# bord.net
KiCad netlist of a schematic drawn in EAGLE
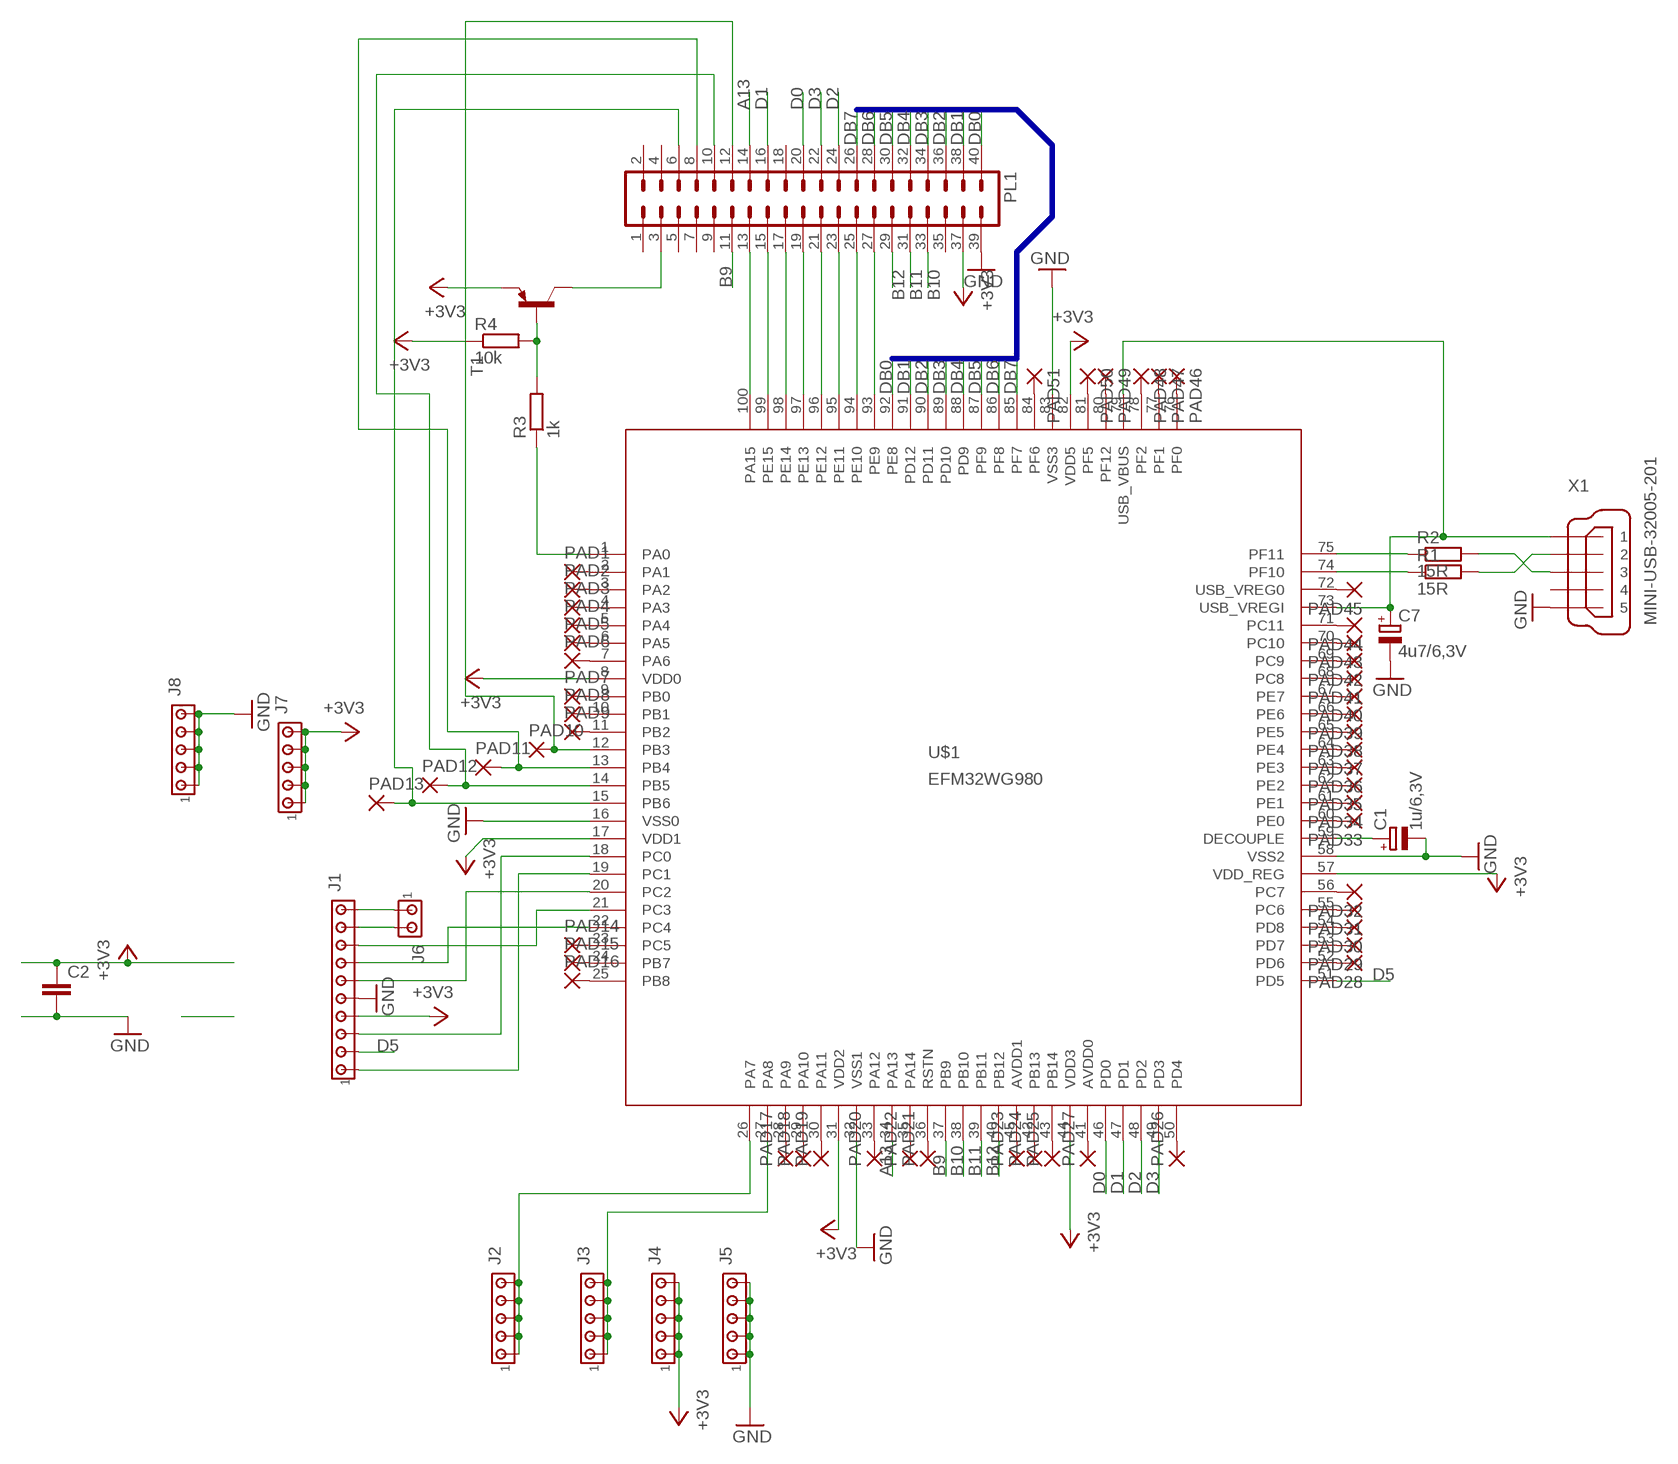
[diagram p0: schematic, sheet 1]

(export (version "E")
  (design (tool "Eeschema 10.0.6"))
  (components
    (comp (ref "C1")
      (value "1u/6,3V")
      (footprint "eagle-import:SMC_B")
      (libsource (lib "eagle-import") (part "CPOL-EUSMCB"))
    )
    (comp (ref "C2")
      (value "C-EUC0603")
      (footprint "eagle-import:C0603")
      (libsource (lib "eagle-import") (part "C-EUC0603"))
    )
    (comp (ref "C7")
      (value "4u7/6,3V")
      (footprint "eagle-import:SMC_B")
      (libsource (lib "eagle-import") (part "CPOL-EUSMCB"))
    )
    (comp (ref "J1")
      (value "MTA10-100")
      (footprint "eagle-import:10X10MTA")
      (libsource (lib "eagle-import") (part "MTA10-100"))
    )
    (comp (ref "J2")
      (value "MTA05-100")
      (footprint "eagle-import:10X05MTA")
      (libsource (lib "eagle-import") (part "MTA05-100"))
    )
    (comp (ref "J3")
      (value "MTA05-100")
      (footprint "eagle-import:10X05MTA")
      (libsource (lib "eagle-import") (part "MTA05-100"))
    )
    (comp (ref "J4")
      (value "MTA05-100")
      (footprint "eagle-import:10X05MTA")
      (libsource (lib "eagle-import") (part "MTA05-100"))
    )
    (comp (ref "J5")
      (value "MTA05-100")
      (footprint "eagle-import:10X05MTA")
      (libsource (lib "eagle-import") (part "MTA05-100"))
    )
    (comp (ref "J6")
      (value "MTA02-100")
      (footprint "eagle-import:10X02MTA")
      (libsource (lib "eagle-import") (part "MTA02-100"))
    )
    (comp (ref "J7")
      (value "MTA05-100")
      (footprint "eagle-import:10X05MTA")
      (libsource (lib "eagle-import") (part "MTA05-100"))
    )
    (comp (ref "J8")
      (value "MTA05-100")
      (footprint "eagle-import:10X05MTA")
      (libsource (lib "eagle-import") (part "MTA05-100"))
    )
    (comp (ref "PAD1")
      (value "1,6/0,8")
      (footprint "eagle-import:1,6_0,8")
      (libsource (lib "eagle-import") (part "1,6/0,8"))
    )
    (comp (ref "PAD2")
      (value "1,6/0,8")
      (footprint "eagle-import:1,6_0,8")
      (libsource (lib "eagle-import") (part "1,6/0,8"))
    )
    (comp (ref "PAD3")
      (value "1,6/0,8")
      (footprint "eagle-import:1,6_0,8")
      (libsource (lib "eagle-import") (part "1,6/0,8"))
    )
    (comp (ref "PAD4")
      (value "1,6/0,8")
      (footprint "eagle-import:1,6_0,8")
      (libsource (lib "eagle-import") (part "1,6/0,8"))
    )
    (comp (ref "PAD5")
      (value "1,6/0,8")
      (footprint "eagle-import:1,6_0,8")
      (libsource (lib "eagle-import") (part "1,6/0,8"))
    )
    (comp (ref "PAD6")
      (value "1,6/0,8")
      (footprint "eagle-import:1,6_0,8")
      (libsource (lib "eagle-import") (part "1,6/0,8"))
    )
    (comp (ref "PAD7")
      (value "1,6/0,8")
      (footprint "eagle-import:1,6_0,8")
      (libsource (lib "eagle-import") (part "1,6/0,8"))
    )
    (comp (ref "PAD8")
      (value "1,6/0,8")
      (footprint "eagle-import:1,6_0,8")
      (libsource (lib "eagle-import") (part "1,6/0,8"))
    )
    (comp (ref "PAD9")
      (value "1,6/0,8")
      (footprint "eagle-import:1,6_0,8")
      (libsource (lib "eagle-import") (part "1,6/0,8"))
    )
    (comp (ref "PAD10")
      (value "1,6/0,8")
      (footprint "eagle-import:1,6_0,8")
      (libsource (lib "eagle-import") (part "1,6/0,8"))
    )
    (comp (ref "PAD11")
      (value "1,6/0,8")
      (footprint "eagle-import:1,6_0,8")
      (libsource (lib "eagle-import") (part "1,6/0,8"))
    )
    (comp (ref "PAD12")
      (value "1,6/0,8")
      (footprint "eagle-import:1,6_0,8")
      (libsource (lib "eagle-import") (part "1,6/0,8"))
    )
    (comp (ref "PAD13")
      (value "1,6/0,8")
      (footprint "eagle-import:1,6_0,8")
      (libsource (lib "eagle-import") (part "1,6/0,8"))
    )
    (comp (ref "PAD14")
      (value "1,6/0,8")
      (footprint "eagle-import:1,6_0,8")
      (libsource (lib "eagle-import") (part "1,6/0,8"))
    )
    (comp (ref "PAD15")
      (value "1,6/0,8")
      (footprint "eagle-import:1,6_0,8")
      (libsource (lib "eagle-import") (part "1,6/0,8"))
    )
    (comp (ref "PAD16")
      (value "1,6/0,8")
      (footprint "eagle-import:1,6_0,8")
      (libsource (lib "eagle-import") (part "1,6/0,8"))
    )
    (comp (ref "PAD17")
      (value "1,6/0,8")
      (footprint "eagle-import:1,6_0,8")
      (libsource (lib "eagle-import") (part "1,6/0,8"))
    )
    (comp (ref "PAD18")
      (value "1,6/0,8")
      (footprint "eagle-import:1,6_0,8")
      (libsource (lib "eagle-import") (part "1,6/0,8"))
    )
    (comp (ref "PAD19")
      (value "1,6/0,8")
      (footprint "eagle-import:1,6_0,8")
      (libsource (lib "eagle-import") (part "1,6/0,8"))
    )
    (comp (ref "PAD20")
      (value "1,6/0,8")
      (footprint "eagle-import:1,6_0,8")
      (libsource (lib "eagle-import") (part "1,6/0,8"))
    )
    (comp (ref "PAD21")
      (value "1,6/0,8")
      (footprint "eagle-import:1,6_0,8")
      (libsource (lib "eagle-import") (part "1,6/0,8"))
    )
    (comp (ref "PAD22")
      (value "1,6/0,8")
      (footprint "eagle-import:1,6_0,8")
      (libsource (lib "eagle-import") (part "1,6/0,8"))
    )
    (comp (ref "PAD23")
      (value "1,6/0,8")
      (footprint "eagle-import:1,6_0,8")
      (libsource (lib "eagle-import") (part "1,6/0,8"))
    )
    (comp (ref "PAD24")
      (value "1,6/0,8")
      (footprint "eagle-import:1,6_0,8")
      (libsource (lib "eagle-import") (part "1,6/0,8"))
    )
    (comp (ref "PAD25")
      (value "1,6/0,8")
      (footprint "eagle-import:1,6_0,8")
      (libsource (lib "eagle-import") (part "1,6/0,8"))
    )
    (comp (ref "PAD26")
      (value "1,6/0,8")
      (footprint "eagle-import:1,6_0,8")
      (libsource (lib "eagle-import") (part "1,6/0,8"))
    )
    (comp (ref "PAD27")
      (value "1,6/0,8")
      (footprint "eagle-import:1,6_0,8")
      (libsource (lib "eagle-import") (part "1,6/0,8"))
    )
    (comp (ref "PAD28")
      (value "1,6/0,8")
      (footprint "eagle-import:1,6_0,8")
      (libsource (lib "eagle-import") (part "1,6/0,8"))
    )
    (comp (ref "PAD29")
      (value "1,6/0,8")
      (footprint "eagle-import:1,6_0,8")
      (libsource (lib "eagle-import") (part "1,6/0,8"))
    )
    (comp (ref "PAD30")
      (value "1,6/0,8")
      (footprint "eagle-import:1,6_0,8")
      (libsource (lib "eagle-import") (part "1,6/0,8"))
    )
    (comp (ref "PAD31")
      (value "1,6/0,8")
      (footprint "eagle-import:1,6_0,8")
      (libsource (lib "eagle-import") (part "1,6/0,8"))
    )
    (comp (ref "PAD32")
      (value "1,6/0,8")
      (footprint "eagle-import:1,6_0,8")
      (libsource (lib "eagle-import") (part "1,6/0,8"))
    )
    (comp (ref "PAD33")
      (value "1,6/0,8")
      (footprint "eagle-import:1,6_0,8")
      (libsource (lib "eagle-import") (part "1,6/0,8"))
    )
    (comp (ref "PAD34")
      (value "1,6/0,8")
      (footprint "eagle-import:1,6_0,8")
      (libsource (lib "eagle-import") (part "1,6/0,8"))
    )
    (comp (ref "PAD35")
      (value "1,6/0,8")
      (footprint "eagle-import:1,6_0,8")
      (libsource (lib "eagle-import") (part "1,6/0,8"))
    )
    (comp (ref "PAD36")
      (value "1,6/0,8")
      (footprint "eagle-import:1,6_0,8")
      (libsource (lib "eagle-import") (part "1,6/0,8"))
    )
    (comp (ref "PAD37")
      (value "1,6/0,8")
      (footprint "eagle-import:1,6_0,8")
      (libsource (lib "eagle-import") (part "1,6/0,8"))
    )
    (comp (ref "PAD38")
      (value "1,6/0,8")
      (footprint "eagle-import:1,6_0,8")
      (libsource (lib "eagle-import") (part "1,6/0,8"))
    )
    (comp (ref "PAD39")
      (value "1,6/0,8")
      (footprint "eagle-import:1,6_0,8")
      (libsource (lib "eagle-import") (part "1,6/0,8"))
    )
    (comp (ref "PAD40")
      (value "1,6/0,8")
      (footprint "eagle-import:1,6_0,8")
      (libsource (lib "eagle-import") (part "1,6/0,8"))
    )
    (comp (ref "PAD41")
      (value "1,6/0,8")
      (footprint "eagle-import:1,6_0,8")
      (libsource (lib "eagle-import") (part "1,6/0,8"))
    )
    (comp (ref "PAD42")
      (value "1,6/0,8")
      (footprint "eagle-import:1,6_0,8")
      (libsource (lib "eagle-import") (part "1,6/0,8"))
    )
    (comp (ref "PAD43")
      (value "1,6/0,8")
      (footprint "eagle-import:1,6_0,8")
      (libsource (lib "eagle-import") (part "1,6/0,8"))
    )
    (comp (ref "PAD44")
      (value "1,6/0,8")
      (footprint "eagle-import:1,6_0,8")
      (libsource (lib "eagle-import") (part "1,6/0,8"))
    )
    (comp (ref "PAD45")
      (value "1,6/0,8")
      (footprint "eagle-import:1,6_0,8")
      (libsource (lib "eagle-import") (part "1,6/0,8"))
    )
    (comp (ref "PAD46")
      (value "1,6/0,8")
      (footprint "eagle-import:1,6_0,8")
      (libsource (lib "eagle-import") (part "1,6/0,8"))
    )
    (comp (ref "PAD47")
      (value "1,6/0,8")
      (footprint "eagle-import:1,6_0,8")
      (libsource (lib "eagle-import") (part "1,6/0,8"))
    )
    (comp (ref "PAD48")
      (value "1,6/0,8")
      (footprint "eagle-import:1,6_0,8")
      (libsource (lib "eagle-import") (part "1,6/0,8"))
    )
    (comp (ref "PAD49")
      (value "1,6/0,8")
      (footprint "eagle-import:1,6_0,8")
      (libsource (lib "eagle-import") (part "1,6/0,8"))
    )
    (comp (ref "PAD50")
      (value "1,6/0,8")
      (footprint "eagle-import:1,6_0,8")
      (libsource (lib "eagle-import") (part "1,6/0,8"))
    )
    (comp (ref "PAD51")
      (value "1,6/0,8")
      (footprint "eagle-import:1,6_0,8")
      (libsource (lib "eagle-import") (part "1,6/0,8"))
    )
    (comp (ref "PL1")
      (value "40V")
      (footprint "eagle-import:40V")
      (libsource (lib "eagle-import") (part "40V"))
    )
    (comp (ref "R1")
      (value "15R")
      (footprint "eagle-import:M0805")
      (libsource (lib "eagle-import") (part "R-EU_M0805"))
    )
    (comp (ref "R2")
      (value "15R")
      (footprint "eagle-import:M0805")
      (libsource (lib "eagle-import") (part "R-EU_M0805"))
    )
    (comp (ref "R3")
      (value "1k")
      (footprint "eagle-import:M0805")
      (libsource (lib "eagle-import") (part "R-EU_M0805"))
    )
    (comp (ref "R4")
      (value "10k")
      (footprint "eagle-import:M0805")
      (libsource (lib "eagle-import") (part "R-EU_M0805"))
    )
    (comp (ref "T1")
      (value "BC807-16-PNP-SOT23-BEC")
      (footprint "eagle-import:SOT23-BEC")
      (libsource (lib "eagle-import") (part "-PNP-SOT23-BECBC807-16"))
    )
    (comp (ref "U$1")
      (value "EFM32WG980")
      (footprint "eagle-import:LQFP100")
      (libsource (lib "eagle-import") (part "EFM32WG980"))
    )
    (comp (ref "X1")
      (value "MINI-USB-32005-201")
      (footprint "eagle-import:32005-201")
      (libsource (lib "eagle-import") (part "MINI-USB-32005-201"))
    )
  )
  (nets
    (net (code "1") (name "+3V3") (class "Default")
      (node (ref "C2") (pin "1") (pinfunction "1_1") (pintype "passive"))
      (node (ref "J1") (pin "4") (pinfunction "4_4") (pintype "passive"))
      (node (ref "J4") (pin "1") (pinfunction "1_1") (pintype "passive"))
      (node (ref "J4") (pin "2") (pinfunction "2_2") (pintype "passive"))
      (node (ref "J4") (pin "3") (pinfunction "3_3") (pintype "passive"))
      (node (ref "J4") (pin "4") (pinfunction "4_4") (pintype "passive"))
      (node (ref "J4") (pin "5") (pinfunction "5_5") (pintype "passive"))
      (node (ref "J7") (pin "1") (pinfunction "1_1") (pintype "passive"))
      (node (ref "J7") (pin "2") (pinfunction "2_2") (pintype "passive"))
      (node (ref "J7") (pin "3") (pinfunction "3_3") (pintype "passive"))
      (node (ref "J7") (pin "4") (pinfunction "4_4") (pintype "passive"))
      (node (ref "J7") (pin "5") (pinfunction "5_5") (pintype "passive"))
      (node (ref "PL1") (pin "37") (pinfunction "37_37") (pintype "passive"))
      (node (ref "R4") (pin "1") (pinfunction "1_1") (pintype "passive"))
      (node (ref "T1") (pin "E") (pinfunction "E_E") (pintype "passive"))
      (node (ref "U$1") (pin "17") (pinfunction "VDD1_17") (pintype "power_in"))
      (node (ref "U$1") (pin "31") (pinfunction "VDD2_31") (pintype "power_in"))
      (node (ref "U$1") (pin "44") (pinfunction "VDD3_44") (pintype "power_in"))
      (node (ref "U$1") (pin "57") (pinfunction "VDD_REG_57") (pintype "power_in"))
      (node (ref "U$1") (pin "8") (pinfunction "VDD0_8") (pintype "power_in"))
      (node (ref "U$1") (pin "82") (pinfunction "VDD5_82") (pintype "power_in"))
    )
    (net (code "2") (name "/A13") (class "Default")
      (node (ref "PL1") (pin "14") (pinfunction "14_14") (pintype "passive"))
      (node (ref "U$1") (pin "34") (pinfunction "PA13_34") (pintype "bidirectional"))
    )
    (net (code "3") (name "/B9") (class "Default")
      (node (ref "PL1") (pin "11") (pinfunction "11_11") (pintype "passive"))
      (node (ref "U$1") (pin "37") (pinfunction "PB9_37") (pintype "bidirectional"))
    )
    (net (code "4") (name "/B10") (class "Default")
      (node (ref "PL1") (pin "33") (pinfunction "33_33") (pintype "passive"))
      (node (ref "U$1") (pin "38") (pinfunction "PB10_38") (pintype "bidirectional"))
    )
    (net (code "5") (name "/B11") (class "Default")
      (node (ref "PL1") (pin "31") (pinfunction "31_31") (pintype "passive"))
      (node (ref "U$1") (pin "39") (pinfunction "PB11_39") (pintype "bidirectional"))
    )
    (net (code "6") (name "/B12") (class "Default")
      (node (ref "PL1") (pin "29") (pinfunction "29_29") (pintype "passive"))
      (node (ref "U$1") (pin "40") (pinfunction "PB12_40") (pintype "bidirectional"))
    )
    (net (code "7") (name "/D0") (class "Default")
      (node (ref "PL1") (pin "20") (pinfunction "20_20") (pintype "passive"))
      (node (ref "U$1") (pin "46") (pinfunction "PD0_46") (pintype "bidirectional"))
    )
    (net (code "8") (name "/D1") (class "Default")
      (node (ref "PL1") (pin "16") (pinfunction "16_16") (pintype "passive"))
      (node (ref "U$1") (pin "47") (pinfunction "PD1_47") (pintype "bidirectional"))
    )
    (net (code "9") (name "/D2") (class "Default")
      (node (ref "PL1") (pin "24") (pinfunction "24_24") (pintype "passive"))
      (node (ref "U$1") (pin "48") (pinfunction "PD2_48") (pintype "bidirectional"))
    )
    (net (code "10") (name "/D3") (class "Default")
      (node (ref "PL1") (pin "22") (pinfunction "22_22") (pintype "passive"))
      (node (ref "U$1") (pin "49") (pinfunction "PD3_49") (pintype "bidirectional"))
    )
    (net (code "11") (name "/D5") (class "Default")
      (node (ref "J1") (pin "2") (pinfunction "2_2") (pintype "passive"))
      (node (ref "U$1") (pin "51") (pinfunction "PD5_51") (pintype "bidirectional"))
    )
    (net (code "12") (name "/DB0") (class "Default")
      (node (ref "PL1") (pin "40") (pinfunction "40_40") (pintype "passive"))
      (node (ref "U$1") (pin "92") (pinfunction "PE8_92") (pintype "bidirectional"))
    )
    (net (code "13") (name "/DB1") (class "Default")
      (node (ref "PL1") (pin "38") (pinfunction "38_38") (pintype "passive"))
      (node (ref "U$1") (pin "91") (pinfunction "PD12_91") (pintype "bidirectional"))
    )
    (net (code "14") (name "/DB2") (class "Default")
      (node (ref "PL1") (pin "36") (pinfunction "36_36") (pintype "passive"))
      (node (ref "U$1") (pin "90") (pinfunction "PD11_90") (pintype "power_in"))
    )
    (net (code "15") (name "/DB3") (class "Default")
      (node (ref "PL1") (pin "34") (pinfunction "34_34") (pintype "passive"))
      (node (ref "U$1") (pin "89") (pinfunction "PD10_89") (pintype "bidirectional"))
    )
    (net (code "16") (name "/DB4") (class "Default")
      (node (ref "PL1") (pin "32") (pinfunction "32_32") (pintype "passive"))
      (node (ref "U$1") (pin "88") (pinfunction "PD9_88") (pintype "bidirectional"))
    )
    (net (code "17") (name "/DB5") (class "Default")
      (node (ref "PL1") (pin "30") (pinfunction "30_30") (pintype "passive"))
      (node (ref "U$1") (pin "87") (pinfunction "PF9_87") (pintype "bidirectional"))
    )
    (net (code "18") (name "/DB6") (class "Default")
      (node (ref "PL1") (pin "28") (pinfunction "28_28") (pintype "passive"))
      (node (ref "U$1") (pin "86") (pinfunction "PF8_86") (pintype "bidirectional"))
    )
    (net (code "19") (name "/DB7") (class "Default")
      (node (ref "PL1") (pin "26") (pinfunction "26_26") (pintype "passive"))
      (node (ref "U$1") (pin "85") (pinfunction "PF7_85") (pintype "bidirectional"))
    )
    (net (code "20") (name "GND") (class "Default")
      (node (ref "C1") (pin "-") (pinfunction "-_-") (pintype "passive"))
      (node (ref "C2") (pin "2") (pinfunction "2_2") (pintype "passive"))
      (node (ref "C7") (pin "-") (pinfunction "-_-") (pintype "passive"))
      (node (ref "J1") (pin "5") (pinfunction "5_5") (pintype "passive"))
      (node (ref "J5") (pin "1") (pinfunction "1_1") (pintype "passive"))
      (node (ref "J5") (pin "2") (pinfunction "2_2") (pintype "passive"))
      (node (ref "J5") (pin "3") (pinfunction "3_3") (pintype "passive"))
      (node (ref "J5") (pin "4") (pinfunction "4_4") (pintype "passive"))
      (node (ref "J5") (pin "5") (pinfunction "5_5") (pintype "passive"))
      (node (ref "J8") (pin "1") (pinfunction "1_1") (pintype "passive"))
      (node (ref "J8") (pin "2") (pinfunction "2_2") (pintype "passive"))
      (node (ref "J8") (pin "3") (pinfunction "3_3") (pintype "passive"))
      (node (ref "J8") (pin "4") (pinfunction "4_4") (pintype "passive"))
      (node (ref "J8") (pin "5") (pinfunction "5_5") (pintype "passive"))
      (node (ref "PL1") (pin "39") (pinfunction "39_39") (pintype "passive"))
      (node (ref "U$1") (pin "16") (pinfunction "VSS0_16") (pintype "power_in"))
      (node (ref "U$1") (pin "32") (pinfunction "VSS1_32") (pintype "power_in"))
      (node (ref "U$1") (pin "58") (pinfunction "VSS2_58") (pintype "power_in"))
      (node (ref "U$1") (pin "83") (pinfunction "VSS3_83") (pintype "bidirectional"))
      (node (ref "X1") (pin "5") (pinfunction "5_5") (pintype "passive"))
    )
    (net (code "21") (name "Net-(J1-Pad9)") (class "Default")
      (node (ref "J1") (pin "9") (pinfunction "9_9") (pintype "passive"))
      (node (ref "J6") (pin "2") (pinfunction "2_2") (pintype "passive"))
    )
    (net (code "22") (name "Net-(J1-Pad10)") (class "Default")
      (node (ref "J1") (pin "10") (pinfunction "10_10") (pintype "passive"))
      (node (ref "J6") (pin "1") (pinfunction "1_1") (pintype "passive"))
    )
    (net (code "23") (name "Net-(PAD1-P)") (class "Default")
      (node (ref "PAD1") (pin "1") (pinfunction "P_1") (pintype "passive"))
      (node (ref "U$1") (pin "2") (pinfunction "PA1_2") (pintype "bidirectional"))
    )
    (net (code "24") (name "Net-(PAD2-P)") (class "Default")
      (node (ref "PAD2") (pin "1") (pinfunction "P_1") (pintype "passive"))
      (node (ref "U$1") (pin "3") (pinfunction "PA2_3") (pintype "bidirectional"))
    )
    (net (code "25") (name "Net-(PAD3-P)") (class "Default")
      (node (ref "PAD3") (pin "1") (pinfunction "P_1") (pintype "passive"))
      (node (ref "U$1") (pin "4") (pinfunction "PA3_4") (pintype "bidirectional"))
    )
    (net (code "26") (name "Net-(PAD4-P)") (class "Default")
      (node (ref "PAD4") (pin "1") (pinfunction "P_1") (pintype "passive"))
      (node (ref "U$1") (pin "5") (pinfunction "PA4_5") (pintype "bidirectional"))
    )
    (net (code "27") (name "Net-(PAD5-P)") (class "Default")
      (node (ref "PAD5") (pin "1") (pinfunction "P_1") (pintype "passive"))
      (node (ref "U$1") (pin "6") (pinfunction "PA5_6") (pintype "bidirectional"))
    )
    (net (code "28") (name "Net-(PAD6-P)") (class "Default")
      (node (ref "PAD6") (pin "1") (pinfunction "P_1") (pintype "passive"))
      (node (ref "U$1") (pin "7") (pinfunction "PA6_7") (pintype "bidirectional"))
    )
    (net (code "29") (name "Net-(PAD7-P)") (class "Default")
      (node (ref "PAD7") (pin "1") (pinfunction "P_1") (pintype "passive"))
      (node (ref "U$1") (pin "9") (pinfunction "PB0_9") (pintype "bidirectional"))
    )
    (net (code "30") (name "Net-(PAD8-P)") (class "Default")
      (node (ref "PAD8") (pin "1") (pinfunction "P_1") (pintype "passive"))
      (node (ref "U$1") (pin "10") (pinfunction "PB1_10") (pintype "bidirectional"))
    )
    (net (code "31") (name "Net-(PAD9-P)") (class "Default")
      (node (ref "PAD9") (pin "1") (pinfunction "P_1") (pintype "passive"))
      (node (ref "U$1") (pin "11") (pinfunction "PB2_11") (pintype "bidirectional"))
    )
    (net (code "32") (name "Net-(PAD10-P)") (class "Default")
      (node (ref "PAD10") (pin "1") (pinfunction "P_1") (pintype "passive"))
      (node (ref "PL1") (pin "12") (pinfunction "12_12") (pintype "passive"))
      (node (ref "U$1") (pin "12") (pinfunction "PB3_12") (pintype "bidirectional"))
    )
    (net (code "33") (name "Net-(PAD11-P)") (class "Default")
      (node (ref "PAD11") (pin "1") (pinfunction "P_1") (pintype "passive"))
      (node (ref "PL1") (pin "8") (pinfunction "8_8") (pintype "passive"))
      (node (ref "U$1") (pin "13") (pinfunction "PB4_13") (pintype "bidirectional"))
    )
    (net (code "34") (name "Net-(PAD12-P)") (class "Default")
      (node (ref "PAD12") (pin "1") (pinfunction "P_1") (pintype "passive"))
      (node (ref "PL1") (pin "10") (pinfunction "10_10") (pintype "passive"))
      (node (ref "U$1") (pin "14") (pinfunction "PB5_14") (pintype "bidirectional"))
    )
    (net (code "35") (name "Net-(PAD13-P)") (class "Default")
      (node (ref "PAD13") (pin "1") (pinfunction "P_1") (pintype "passive"))
      (node (ref "PL1") (pin "6") (pinfunction "6_6") (pintype "passive"))
      (node (ref "U$1") (pin "15") (pinfunction "PB6_15") (pintype "bidirectional"))
    )
    (net (code "36") (name "Net-(PAD14-P)") (class "Default")
      (node (ref "PAD14") (pin "1") (pinfunction "P_1") (pintype "passive"))
      (node (ref "U$1") (pin "23") (pinfunction "PC5_23") (pintype "bidirectional"))
    )
    (net (code "37") (name "Net-(PAD15-P)") (class "Default")
      (node (ref "PAD15") (pin "1") (pinfunction "P_1") (pintype "passive"))
      (node (ref "U$1") (pin "24") (pinfunction "PB7_24") (pintype "bidirectional"))
    )
    (net (code "38") (name "Net-(PAD16-P)") (class "Default")
      (node (ref "PAD16") (pin "1") (pinfunction "P_1") (pintype "passive"))
      (node (ref "U$1") (pin "25") (pinfunction "PB8_25") (pintype "bidirectional"))
    )
    (net (code "39") (name "Net-(PAD17-P)") (class "Default")
      (node (ref "PAD17") (pin "1") (pinfunction "P_1") (pintype "passive"))
      (node (ref "U$1") (pin "28") (pinfunction "PA9_28") (pintype "bidirectional"))
    )
    (net (code "40") (name "Net-(PAD18-P)") (class "Default")
      (node (ref "PAD18") (pin "1") (pinfunction "P_1") (pintype "passive"))
      (node (ref "U$1") (pin "29") (pinfunction "PA10_29") (pintype "bidirectional"))
    )
    (net (code "41") (name "Net-(PAD19-P)") (class "Default")
      (node (ref "PAD19") (pin "1") (pinfunction "P_1") (pintype "passive"))
      (node (ref "U$1") (pin "30") (pinfunction "PA11_30") (pintype "bidirectional"))
    )
    (net (code "42") (name "Net-(PAD20-P)") (class "Default")
      (node (ref "PAD20") (pin "1") (pinfunction "P_1") (pintype "passive"))
      (node (ref "U$1") (pin "33") (pinfunction "PA12_33") (pintype "bidirectional"))
    )
    (net (code "43") (name "Net-(PAD21-P)") (class "Default")
      (node (ref "PAD21") (pin "1") (pinfunction "P_1") (pintype "passive"))
      (node (ref "U$1") (pin "36") (pinfunction "RSTN_36") (pintype "bidirectional"))
    )
    (net (code "44") (name "Net-(PAD22-P)") (class "Default")
      (node (ref "PAD22") (pin "1") (pinfunction "P_1") (pintype "passive"))
      (node (ref "U$1") (pin "35") (pinfunction "PA14_35") (pintype "bidirectional"))
    )
    (net (code "45") (name "Net-(PAD23-P)") (class "Default")
      (node (ref "PAD23") (pin "1") (pinfunction "P_1") (pintype "passive"))
      (node (ref "U$1") (pin "45") (pinfunction "AVDD1_45") (pintype "bidirectional"))
    )
    (net (code "46") (name "Net-(PAD24-P)") (class "Default")
      (node (ref "PAD24") (pin "1") (pinfunction "P_1") (pintype "passive"))
      (node (ref "U$1") (pin "42") (pinfunction "PB13_42") (pintype "bidirectional"))
    )
    (net (code "47") (name "Net-(PAD25-P)") (class "Default")
      (node (ref "PAD25") (pin "1") (pinfunction "P_1") (pintype "passive"))
      (node (ref "U$1") (pin "43") (pinfunction "PB14_43") (pintype "bidirectional"))
    )
    (net (code "48") (name "Net-(PAD26-P)") (class "Default")
      (node (ref "PAD26") (pin "1") (pinfunction "P_1") (pintype "passive"))
      (node (ref "U$1") (pin "50") (pinfunction "PD4_50") (pintype "bidirectional"))
    )
    (net (code "49") (name "Net-(PAD27-P)") (class "Default")
      (node (ref "PAD27") (pin "1") (pinfunction "P_1") (pintype "passive"))
      (node (ref "U$1") (pin "41") (pinfunction "AVDD0_41") (pintype "power_in"))
    )
    (net (code "50") (name "Net-(PAD28-P)") (class "Default")
      (node (ref "PAD28") (pin "1") (pinfunction "P_1") (pintype "passive"))
      (node (ref "U$1") (pin "52") (pinfunction "PD6_52") (pintype "bidirectional"))
    )
    (net (code "51") (name "Net-(PAD29-P)") (class "Default")
      (node (ref "PAD29") (pin "1") (pinfunction "P_1") (pintype "passive"))
      (node (ref "U$1") (pin "53") (pinfunction "PD7_53") (pintype "bidirectional"))
    )
    (net (code "52") (name "Net-(PAD30-P)") (class "Default")
      (node (ref "PAD30") (pin "1") (pinfunction "P_1") (pintype "passive"))
      (node (ref "U$1") (pin "54") (pinfunction "PD8_54") (pintype "bidirectional"))
    )
    (net (code "53") (name "Net-(PAD31-P)") (class "Default")
      (node (ref "PAD31") (pin "1") (pinfunction "P_1") (pintype "passive"))
      (node (ref "U$1") (pin "55") (pinfunction "PC6_55") (pintype "bidirectional"))
    )
    (net (code "54") (name "Net-(PAD32-P)") (class "Default")
      (node (ref "PAD32") (pin "1") (pinfunction "P_1") (pintype "passive"))
      (node (ref "U$1") (pin "56") (pinfunction "PC7_56") (pintype "bidirectional"))
    )
    (net (code "55") (name "Net-(PAD33-P)") (class "Default")
      (node (ref "PAD33") (pin "1") (pinfunction "P_1") (pintype "passive"))
      (node (ref "U$1") (pin "60") (pinfunction "PE0_60") (pintype "power_in"))
    )
    (net (code "56") (name "Net-(PAD34-P)") (class "Default")
      (node (ref "PAD34") (pin "1") (pinfunction "P_1") (pintype "passive"))
      (node (ref "U$1") (pin "61") (pinfunction "PE1_61") (pintype "bidirectional"))
    )
    (net (code "57") (name "Net-(PAD35-P)") (class "Default")
      (node (ref "PAD35") (pin "1") (pinfunction "P_1") (pintype "passive"))
      (node (ref "U$1") (pin "62") (pinfunction "PE2_62") (pintype "bidirectional"))
    )
    (net (code "58") (name "Net-(PAD36-P)") (class "Default")
      (node (ref "PAD36") (pin "1") (pinfunction "P_1") (pintype "passive"))
      (node (ref "U$1") (pin "63") (pinfunction "PE3_63") (pintype "bidirectional"))
    )
    (net (code "59") (name "Net-(PAD37-P)") (class "Default")
      (node (ref "PAD37") (pin "1") (pinfunction "P_1") (pintype "passive"))
      (node (ref "U$1") (pin "64") (pinfunction "PE4_64") (pintype "bidirectional"))
    )
    (net (code "60") (name "Net-(PAD38-P)") (class "Default")
      (node (ref "PAD38") (pin "1") (pinfunction "P_1") (pintype "passive"))
      (node (ref "U$1") (pin "65") (pinfunction "PE5_65") (pintype "power_in"))
    )
    (net (code "61") (name "Net-(PAD39-P)") (class "Default")
      (node (ref "PAD39") (pin "1") (pinfunction "P_1") (pintype "passive"))
      (node (ref "U$1") (pin "66") (pinfunction "PE6_66") (pintype "bidirectional"))
    )
    (net (code "62") (name "Net-(PAD40-P)") (class "Default")
      (node (ref "PAD40") (pin "1") (pinfunction "P_1") (pintype "passive"))
      (node (ref "U$1") (pin "67") (pinfunction "PE7_67") (pintype "bidirectional"))
    )
    (net (code "63") (name "Net-(PAD41-P)") (class "Default")
      (node (ref "PAD41") (pin "1") (pinfunction "P_1") (pintype "passive"))
      (node (ref "U$1") (pin "68") (pinfunction "PC8_68") (pintype "power_in"))
    )
    (net (code "64") (name "Net-(PAD42-P)") (class "Default")
      (node (ref "PAD42") (pin "1") (pinfunction "P_1") (pintype "passive"))
      (node (ref "U$1") (pin "69") (pinfunction "PC9_69") (pintype "bidirectional"))
    )
    (net (code "65") (name "Net-(PAD43-P)") (class "Default")
      (node (ref "PAD43") (pin "1") (pinfunction "P_1") (pintype "passive"))
      (node (ref "U$1") (pin "70") (pinfunction "PC10_70") (pintype "bidirectional"))
    )
    (net (code "66") (name "Net-(PAD44-P)") (class "Default")
      (node (ref "PAD44") (pin "1") (pinfunction "P_1") (pintype "passive"))
      (node (ref "U$1") (pin "71") (pinfunction "PC11_71") (pintype "power_in"))
    )
    (net (code "67") (name "Net-(PAD45-P)") (class "Default")
      (node (ref "PAD45") (pin "1") (pinfunction "P_1") (pintype "passive"))
      (node (ref "U$1") (pin "72") (pinfunction "USB_VREG0_72") (pintype "power_in"))
    )
    (net (code "68") (name "Net-(PAD46-P)") (class "Default")
      (node (ref "PAD46") (pin "1") (pinfunction "P_1") (pintype "passive"))
      (node (ref "U$1") (pin "76") (pinfunction "PF0_76") (pintype "input"))
    )
    (net (code "69") (name "Net-(PAD47-P)") (class "Default")
      (node (ref "PAD47") (pin "1") (pinfunction "P_1") (pintype "passive"))
      (node (ref "U$1") (pin "77") (pinfunction "PF1_77") (pintype "power_in"))
    )
    (net (code "70") (name "Net-(PAD48-P)") (class "Default")
      (node (ref "PAD48") (pin "1") (pinfunction "P_1") (pintype "passive"))
      (node (ref "U$1") (pin "78") (pinfunction "PF2_78") (pintype "bidirectional"))
    )
    (net (code "71") (name "Net-(PAD49-P)") (class "Default")
      (node (ref "PAD49") (pin "1") (pinfunction "P_1") (pintype "passive"))
      (node (ref "U$1") (pin "80") (pinfunction "PF12_80") (pintype "bidirectional"))
    )
    (net (code "72") (name "Net-(PAD50-P)") (class "Default")
      (node (ref "PAD50") (pin "1") (pinfunction "P_1") (pintype "passive"))
      (node (ref "U$1") (pin "81") (pinfunction "PF5_81") (pintype "bidirectional"))
    )
    (net (code "73") (name "Net-(PAD51-P)") (class "Default")
      (node (ref "PAD51") (pin "1") (pinfunction "P_1") (pintype "passive"))
      (node (ref "U$1") (pin "84") (pinfunction "PF6_84") (pintype "power_in"))
    )
    (net (code "74") (name "Net-(PL1-Pad3)") (class "Default")
      (node (ref "PL1") (pin "3") (pinfunction "3_3") (pintype "passive"))
      (node (ref "T1") (pin "C") (pinfunction "C_C") (pintype "passive"))
    )
    (net (code "75") (name "Net-(R1-Pad2)") (class "Default")
      (node (ref "R1") (pin "2") (pinfunction "2_2") (pintype "passive"))
      (node (ref "X1") (pin "2") (pinfunction "2_2") (pintype "passive"))
    )
    (net (code "76") (name "Net-(R2-Pad2)") (class "Default")
      (node (ref "R2") (pin "2") (pinfunction "2_2") (pintype "passive"))
      (node (ref "X1") (pin "3") (pinfunction "3_3") (pintype "passive"))
    )
    (net (code "77") (name "Net-(R3-Pad2)") (class "Default")
      (node (ref "R3") (pin "2") (pinfunction "2_2") (pintype "passive"))
      (node (ref "R4") (pin "2") (pinfunction "2_2") (pintype "passive"))
      (node (ref "T1") (pin "B") (pinfunction "B_B") (pintype "passive"))
    )
    (net (code "78") (name "Net-(U$1-DECOUPLE)") (class "Default")
      (node (ref "C1") (pin "+") (pinfunction "+_+") (pintype "passive"))
      (node (ref "U$1") (pin "59") (pinfunction "DECOUPLE_59") (pintype "power_in"))
    )
    (net (code "79") (name "Net-(U$1-PA0)") (class "Default")
      (node (ref "R3") (pin "1") (pinfunction "1_1") (pintype "passive"))
      (node (ref "U$1") (pin "1") (pinfunction "PA0_1") (pintype "bidirectional"))
    )
    (net (code "80") (name "Net-(U$1-PA7)") (class "Default")
      (node (ref "J2") (pin "1") (pinfunction "1_1") (pintype "passive"))
      (node (ref "J2") (pin "2") (pinfunction "2_2") (pintype "passive"))
      (node (ref "J2") (pin "3") (pinfunction "3_3") (pintype "passive"))
      (node (ref "J2") (pin "4") (pinfunction "4_4") (pintype "passive"))
      (node (ref "J2") (pin "5") (pinfunction "5_5") (pintype "passive"))
      (node (ref "U$1") (pin "26") (pinfunction "PA7_26") (pintype "bidirectional"))
    )
    (net (code "81") (name "Net-(U$1-PA8)") (class "Default")
      (node (ref "J3") (pin "1") (pinfunction "1_1") (pintype "passive"))
      (node (ref "J3") (pin "2") (pinfunction "2_2") (pintype "passive"))
      (node (ref "J3") (pin "3") (pinfunction "3_3") (pintype "passive"))
      (node (ref "J3") (pin "4") (pinfunction "4_4") (pintype "passive"))
      (node (ref "J3") (pin "5") (pinfunction "5_5") (pintype "passive"))
      (node (ref "U$1") (pin "27") (pinfunction "PA8_27") (pintype "bidirectional"))
    )
    (net (code "82") (name "Net-(U$1-PA15)") (class "Default")
      (node (ref "PL1") (pin "13") (pinfunction "13_13") (pintype "passive"))
      (node (ref "U$1") (pin "100") (pinfunction "PA15_100") (pintype "input"))
    )
    (net (code "83") (name "Net-(U$1-PC0)") (class "Default")
      (node (ref "J1") (pin "3") (pinfunction "3_3") (pintype "passive"))
      (node (ref "U$1") (pin "18") (pinfunction "PC0_18") (pintype "bidirectional"))
    )
    (net (code "84") (name "Net-(U$1-PC1)") (class "Default")
      (node (ref "J1") (pin "1") (pinfunction "1_1") (pintype "passive"))
      (node (ref "U$1") (pin "19") (pinfunction "PC1_19") (pintype "bidirectional"))
    )
    (net (code "85") (name "Net-(U$1-PC2)") (class "Default")
      (node (ref "J1") (pin "6") (pinfunction "6_6") (pintype "passive"))
      (node (ref "U$1") (pin "20") (pinfunction "PC2_20") (pintype "bidirectional"))
    )
    (net (code "86") (name "Net-(U$1-PC3)") (class "Default")
      (node (ref "J1") (pin "8") (pinfunction "8_8") (pintype "passive"))
      (node (ref "U$1") (pin "21") (pinfunction "PC3_21") (pintype "bidirectional"))
    )
    (net (code "87") (name "Net-(U$1-PC4)") (class "Default")
      (node (ref "J1") (pin "7") (pinfunction "7_7") (pintype "passive"))
      (node (ref "U$1") (pin "22") (pinfunction "PC4_22") (pintype "bidirectional"))
    )
    (net (code "88") (name "Net-(U$1-PE9)") (class "Default")
      (node (ref "PL1") (pin "27") (pinfunction "27_27") (pintype "passive"))
      (node (ref "U$1") (pin "93") (pinfunction "PE9_93") (pintype "bidirectional"))
    )
    (net (code "89") (name "Net-(U$1-PE10)") (class "Default")
      (node (ref "PL1") (pin "25") (pinfunction "25_25") (pintype "passive"))
      (node (ref "U$1") (pin "94") (pinfunction "PE10_94") (pintype "power_in"))
    )
    (net (code "90") (name "Net-(U$1-PE11)") (class "Default")
      (node (ref "PL1") (pin "23") (pinfunction "23_23") (pintype "passive"))
      (node (ref "U$1") (pin "95") (pinfunction "PE11_95") (pintype "bidirectional"))
    )
    (net (code "91") (name "Net-(U$1-PE12)") (class "Default")
      (node (ref "PL1") (pin "21") (pinfunction "21_21") (pintype "passive"))
      (node (ref "U$1") (pin "96") (pinfunction "PE12_96") (pintype "bidirectional"))
    )
    (net (code "92") (name "Net-(U$1-PE13)") (class "Default")
      (node (ref "PL1") (pin "19") (pinfunction "19_19") (pintype "passive"))
      (node (ref "U$1") (pin "97") (pinfunction "PE13_97") (pintype "bidirectional"))
    )
    (net (code "93") (name "Net-(U$1-PE14)") (class "Default")
      (node (ref "PL1") (pin "17") (pinfunction "17_17") (pintype "passive"))
      (node (ref "U$1") (pin "98") (pinfunction "PE14_98") (pintype "bidirectional"))
    )
    (net (code "94") (name "Net-(U$1-PE15)") (class "Default")
      (node (ref "PL1") (pin "15") (pinfunction "15_15") (pintype "passive"))
      (node (ref "U$1") (pin "99") (pinfunction "PE15_99") (pintype "power_in"))
    )
    (net (code "95") (name "Net-(U$1-PF10)") (class "Default")
      (node (ref "R1") (pin "1") (pinfunction "1_1") (pintype "passive"))
      (node (ref "U$1") (pin "74") (pinfunction "PF10_74") (pintype "input"))
    )
    (net (code "96") (name "Net-(U$1-PF11)") (class "Default")
      (node (ref "R2") (pin "1") (pinfunction "1_1") (pintype "passive"))
      (node (ref "U$1") (pin "75") (pinfunction "PF11_75") (pintype "input"))
    )
    (net (code "97") (name "Net-(U$1-USB_VBUS)") (class "Default")
      (node (ref "C7") (pin "+") (pinfunction "+_+") (pintype "passive"))
      (node (ref "U$1") (pin "73") (pinfunction "USB_VREGI_73") (pintype "output"))
      (node (ref "U$1") (pin "79") (pinfunction "USB_VBUS_79") (pintype "bidirectional"))
      (node (ref "X1") (pin "1") (pinfunction "1_1") (pintype "passive"))
    )
    (net (code "98") (name "unconnected-(PL1-Pad1)") (class "Default")
      (node (ref "PL1") (pin "1") (pinfunction "1_1") (pintype "passive"))
    )
    (net (code "99") (name "unconnected-(PL1-Pad2)") (class "Default")
      (node (ref "PL1") (pin "2") (pinfunction "2_2") (pintype "passive"))
    )
    (net (code "100") (name "unconnected-(PL1-Pad4)") (class "Default")
      (node (ref "PL1") (pin "4") (pinfunction "4_4") (pintype "passive"))
    )
    (net (code "101") (name "unconnected-(PL1-Pad5)") (class "Default")
      (node (ref "PL1") (pin "5") (pinfunction "5_5") (pintype "passive"))
    )
    (net (code "102") (name "unconnected-(PL1-Pad7)") (class "Default")
      (node (ref "PL1") (pin "7") (pinfunction "7_7") (pintype "passive"))
    )
    (net (code "103") (name "unconnected-(PL1-Pad9)") (class "Default")
      (node (ref "PL1") (pin "9") (pinfunction "9_9") (pintype "passive"))
    )
    (net (code "104") (name "unconnected-(PL1-Pad18)") (class "Default")
      (node (ref "PL1") (pin "18") (pinfunction "18_18") (pintype "passive"))
    )
    (net (code "105") (name "unconnected-(PL1-Pad35)") (class "Default")
      (node (ref "PL1") (pin "35") (pinfunction "35_35") (pintype "passive"))
    )
    (net (code "106") (name "unconnected-(X1-Pad4)") (class "Default")
      (node (ref "X1") (pin "4") (pinfunction "4_4") (pintype "passive"))
    )
  )
)
